# manual_slave.net
KiCad netlist of a schematic drawn in EAGLE
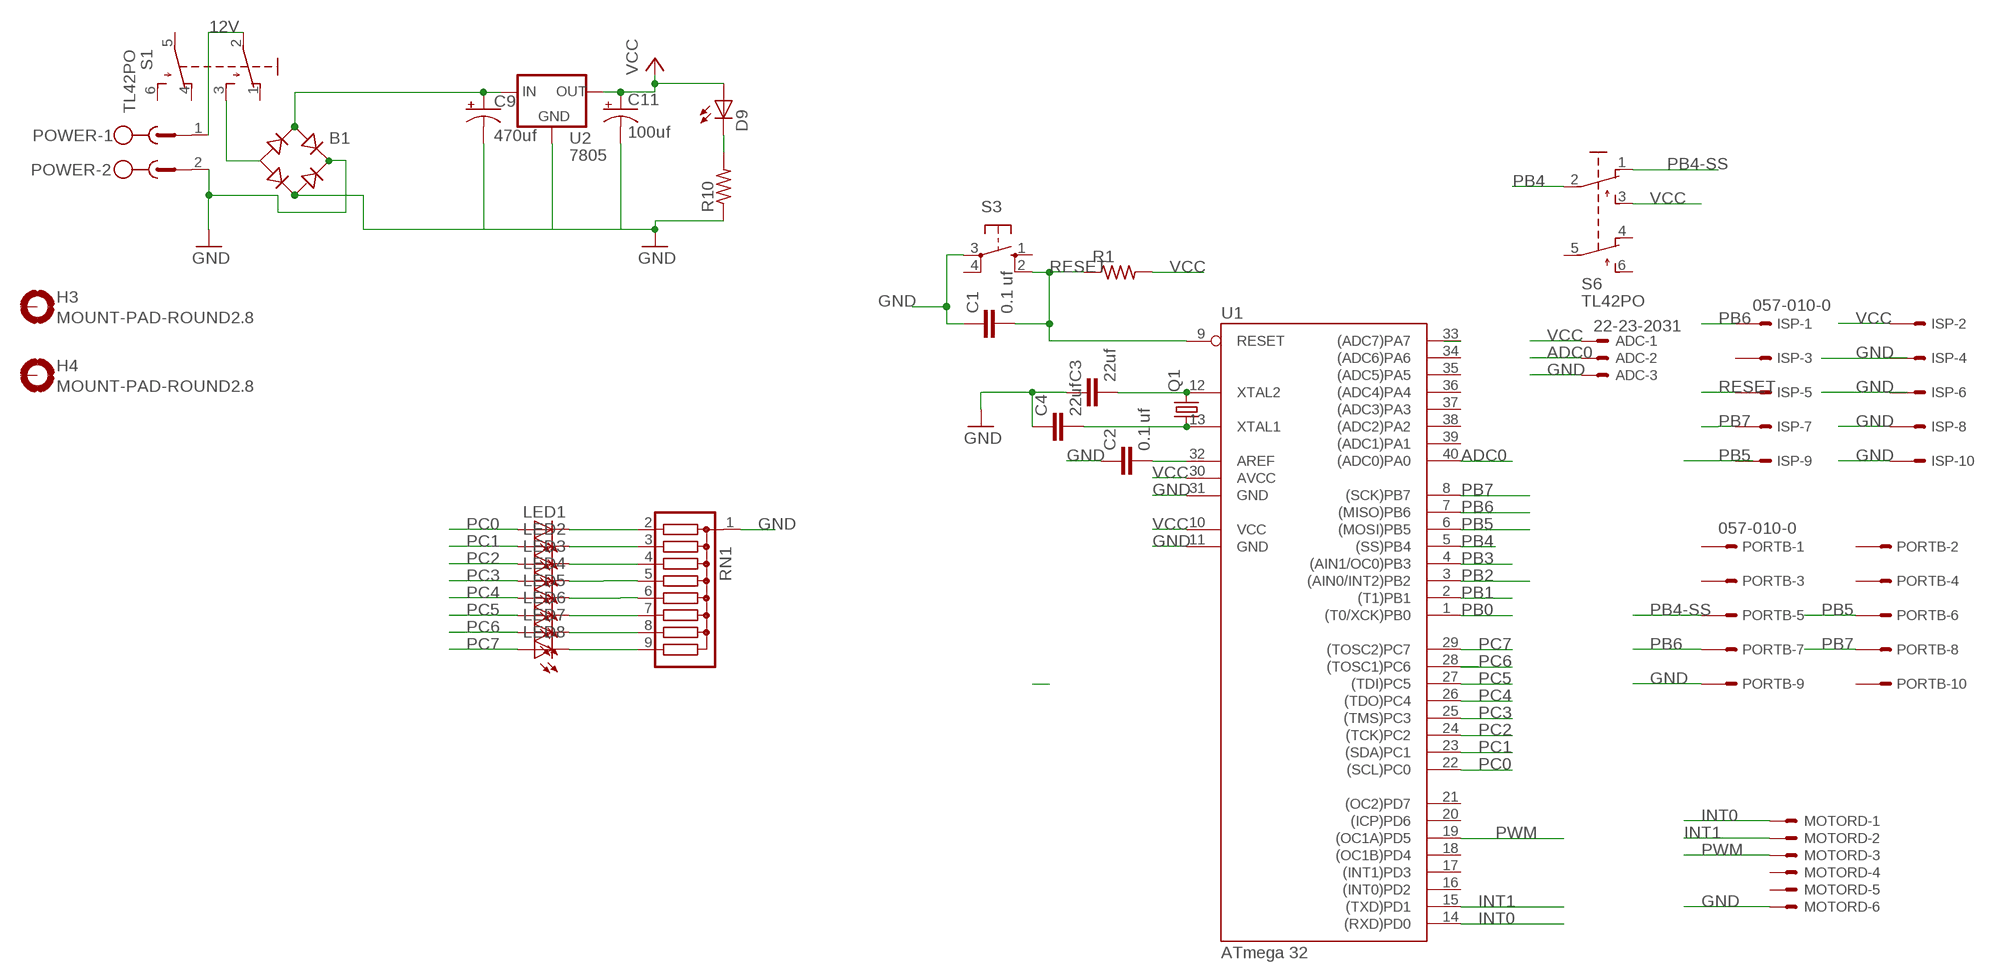
[diagram p0: schematic, sheet 1]

(export (version "E")
  (design (tool "Eeschema 10.0.6"))
  (components
    (comp (ref "ADC")
      (value "22-23-2031")
      (footprint "eagle-import:22-23-2031")
      (fields (field (name "MF") "MOLEX"))
      (libsource (lib "eagle-import") (part "22-23-2031"))
    )
    (comp (ref "B1")
      (value "RB1A")
      (footprint "eagle-import:RB1A")
      (libsource (lib "eagle-import") (part "RB1A"))
    )
    (comp (ref "C1")
      (value "0.1 uf")
      (footprint "eagle-import:C025-024X044")
      (libsource (lib "eagle-import") (part "C-EU025-024X044"))
    )
    (comp (ref "C2")
      (value "0.1 uf")
      (footprint "eagle-import:C025-024X044")
      (libsource (lib "eagle-import") (part "C-EU025-024X044"))
    )
    (comp (ref "C3")
      (value "22uf")
      (footprint "eagle-import:C025-024X044")
      (libsource (lib "eagle-import") (part "C-EU025-024X044"))
    )
    (comp (ref "C4")
      (value "22uf")
      (footprint "eagle-import:C025-024X044")
      (libsource (lib "eagle-import") (part "C-EU025-024X044"))
    )
    (comp (ref "C9")
      (value "470uf")
      (footprint "eagle-import:E2-4")
      (libsource (lib "eagle-import") (part "CPOL-USE2-4"))
    )
    (comp (ref "C11")
      (value "100uf")
      (footprint "eagle-import:E2-4")
      (libsource (lib "eagle-import") (part "CPOL-USE2-4"))
    )
    (comp (ref "D9")
      (value "LED3MM")
      (footprint "eagle-import:LED3MM")
      (libsource (lib "eagle-import") (part "LED3MM"))
    )
    (comp (ref "H3")
      (value "MOUNT-PAD-ROUND2.8")
      (footprint "eagle-import:2,8-PAD")
      (libsource (lib "eagle-import") (part "MOUNT-PAD-ROUND2.8"))
    )
    (comp (ref "H4")
      (value "MOUNT-PAD-ROUND2.8")
      (footprint "eagle-import:2,8-PAD")
      (libsource (lib "eagle-import") (part "MOUNT-PAD-ROUND2.8"))
    )
    (comp (ref "ISP")
      (value "057-010-0")
      (footprint "eagle-import:057-010-0")
      (libsource (lib "eagle-import") (part "057-010-0"))
    )
    (comp (ref "LED1")
      (value "LED3MM")
      (footprint "eagle-import:LED3MM")
      (libsource (lib "eagle-import") (part "LED3MM"))
    )
    (comp (ref "LED2")
      (value "LED3MM")
      (footprint "eagle-import:LED3MM")
      (libsource (lib "eagle-import") (part "LED3MM"))
    )
    (comp (ref "LED3")
      (value "LED3MM")
      (footprint "eagle-import:LED3MM")
      (libsource (lib "eagle-import") (part "LED3MM"))
    )
    (comp (ref "LED4")
      (value "LED3MM")
      (footprint "eagle-import:LED3MM")
      (libsource (lib "eagle-import") (part "LED3MM"))
    )
    (comp (ref "LED5")
      (value "LED3MM")
      (footprint "eagle-import:LED3MM")
      (libsource (lib "eagle-import") (part "LED3MM"))
    )
    (comp (ref "LED6")
      (value "LED3MM")
      (footprint "eagle-import:LED3MM")
      (libsource (lib "eagle-import") (part "LED3MM"))
    )
    (comp (ref "LED7")
      (value "LED3MM")
      (footprint "eagle-import:LED3MM")
      (libsource (lib "eagle-import") (part "LED3MM"))
    )
    (comp (ref "LED8")
      (value "LED3MM")
      (footprint "eagle-import:LED3MM")
      (libsource (lib "eagle-import") (part "LED3MM"))
    )
    (comp (ref "MOTORD")
      (value "22-23-2061")
      (footprint "eagle-import:22-23-2061")
      (fields (field (name "MF") "MOLEX"))
      (libsource (lib "eagle-import") (part "22-23-2061"))
    )
    (comp (ref "PORTB")
      (value "057-010-0")
      (footprint "eagle-import:057-010-0")
      (libsource (lib "eagle-import") (part "057-010-0"))
    )
    (comp (ref "POWER")
      (value "MSTBV2")
      (footprint "eagle-import:MSTBV2")
      (libsource (lib "eagle-import") (part "MSTBV2"))
    )
    (comp (ref "Q1")
      (value "CRYSTALHC18U-V")
      (footprint "eagle-import:HC18U-V")
      (libsource (lib "eagle-import") (part "CRYSTALHC18U-V"))
    )
    (comp (ref "R1")
      (value "R-US_0204/7")
      (footprint "eagle-import:0204_7")
      (libsource (lib "eagle-import") (part "R-US_0204/7"))
    )
    (comp (ref "R10")
      (value "R-US_0204/7")
      (footprint "eagle-import:0204_7")
      (libsource (lib "eagle-import") (part "R-US_0204/7"))
    )
    (comp (ref "RN1")
      (value "G08R")
      (footprint "eagle-import:SIL9")
      (libsource (lib "eagle-import") (part "G08R"))
    )
    (comp (ref "S1")
      (value "TL42PO")
      (footprint "eagle-import:TL4XPO")
      (libsource (lib "eagle-import") (part "TL42PO"))
    )
    (comp (ref "S3")
      (value "10-XX")
      (footprint "eagle-import:B3F-10XX")
      (fields (field (name "MPN") "B3F-1000"))
      (libsource (lib "eagle-import") (part "10-XX"))
    )
    (comp (ref "S6")
      (value "TL42PO")
      (footprint "eagle-import:TL4XPO")
      (libsource (lib "eagle-import") (part "TL42PO"))
    )
    (comp (ref "U1")
      (value "ATmega 32")
      (footprint "eagle-import:DIL40")
      (fields (field (name "MPN") "ATMEGA32-16PU"))
      (libsource (lib "eagle-import") (part "MEGA32-P"))
    )
    (comp (ref "U2")
      (value "7805")
      (footprint "eagle-import:78XXL")
      (libsource (lib "eagle-import") (part "78XXL"))
    )
  )
  (nets
    (net (code "1") (name "/12V") (class "Default")
      (node (ref "POWER") (pin "1") (pinfunction "SK_1") (pintype "passive"))
      (node (ref "S1") (pin "2") (pinfunction "P_2") (pintype "passive"))
    )
    (net (code "2") (name "/ADC0") (class "Default")
      (node (ref "ADC") (pin "2") (pinfunction "S_2") (pintype "passive"))
      (node (ref "U1") (pin "40") (pinfunction "(ADC0)PA0_40") (pintype "bidirectional"))
    )
    (net (code "3") (name "/INT0") (class "Default")
      (node (ref "MOTORD") (pin "1") (pinfunction "S_1") (pintype "passive"))
      (node (ref "U1") (pin "14") (pinfunction "(RXD)PD0_14") (pintype "bidirectional"))
    )
    (net (code "4") (name "/INT1") (class "Default")
      (node (ref "MOTORD") (pin "2") (pinfunction "S_2") (pintype "passive"))
      (node (ref "U1") (pin "15") (pinfunction "(TXD)PD1_15") (pintype "bidirectional"))
    )
    (net (code "5") (name "/PB0") (class "Default")
      (node (ref "U1") (pin "1") (pinfunction "(T0/XCK)PB0_1") (pintype "bidirectional"))
    )
    (net (code "6") (name "/PB1") (class "Default")
      (node (ref "U1") (pin "2") (pinfunction "(T1)PB1_2") (pintype "bidirectional"))
    )
    (net (code "7") (name "/PB2") (class "Default")
      (node (ref "U1") (pin "3") (pinfunction "(AIN0/INT2)PB2_3") (pintype "bidirectional"))
    )
    (net (code "8") (name "/PB3") (class "Default")
      (node (ref "U1") (pin "4") (pinfunction "(AIN1/OC0)PB3_4") (pintype "bidirectional"))
    )
    (net (code "9") (name "/PB4") (class "Default")
      (node (ref "S6") (pin "2") (pinfunction "P_2") (pintype "passive"))
      (node (ref "U1") (pin "5") (pinfunction "(SS)PB4_5") (pintype "bidirectional"))
    )
    (net (code "10") (name "/PB4-SS") (class "Default")
      (node (ref "PORTB") (pin "5") (pinfunction "S_5") (pintype "passive"))
      (node (ref "S6") (pin "1") (pinfunction "O_1") (pintype "passive"))
    )
    (net (code "11") (name "/PB5") (class "Default")
      (node (ref "ISP") (pin "9") (pinfunction "S_9") (pintype "passive"))
      (node (ref "PORTB") (pin "6") (pinfunction "S_6") (pintype "passive"))
      (node (ref "U1") (pin "6") (pinfunction "(MOSI)PB5_6") (pintype "bidirectional"))
    )
    (net (code "12") (name "/PB6") (class "Default")
      (node (ref "ISP") (pin "1") (pinfunction "S_1") (pintype "passive"))
      (node (ref "PORTB") (pin "7") (pinfunction "S_7") (pintype "passive"))
      (node (ref "U1") (pin "7") (pinfunction "(MISO)PB6_7") (pintype "bidirectional"))
    )
    (net (code "13") (name "/PB7") (class "Default")
      (node (ref "ISP") (pin "7") (pinfunction "S_7") (pintype "passive"))
      (node (ref "PORTB") (pin "8") (pinfunction "S_8") (pintype "passive"))
      (node (ref "U1") (pin "8") (pinfunction "(SCK)PB7_8") (pintype "bidirectional"))
    )
    (net (code "14") (name "/PC0") (class "Default")
      (node (ref "LED1") (pin "A") (pinfunction "A_A") (pintype "passive"))
      (node (ref "U1") (pin "22") (pinfunction "(SCL)PC0_22") (pintype "bidirectional"))
    )
    (net (code "15") (name "/PC1") (class "Default")
      (node (ref "LED2") (pin "A") (pinfunction "A_A") (pintype "passive"))
      (node (ref "U1") (pin "23") (pinfunction "(SDA)PC1_23") (pintype "bidirectional"))
    )
    (net (code "16") (name "/PC2") (class "Default")
      (node (ref "LED3") (pin "A") (pinfunction "A_A") (pintype "passive"))
      (node (ref "U1") (pin "24") (pinfunction "(TCK)PC2_24") (pintype "bidirectional"))
    )
    (net (code "17") (name "/PC3") (class "Default")
      (node (ref "LED4") (pin "A") (pinfunction "A_A") (pintype "passive"))
      (node (ref "U1") (pin "25") (pinfunction "(TMS)PC3_25") (pintype "bidirectional"))
    )
    (net (code "18") (name "/PC4") (class "Default")
      (node (ref "LED5") (pin "A") (pinfunction "A_A") (pintype "passive"))
      (node (ref "U1") (pin "26") (pinfunction "(TDO)PC4_26") (pintype "bidirectional"))
    )
    (net (code "19") (name "/PC5") (class "Default")
      (node (ref "LED6") (pin "A") (pinfunction "A_A") (pintype "passive"))
      (node (ref "U1") (pin "27") (pinfunction "(TDI)PC5_27") (pintype "bidirectional"))
    )
    (net (code "20") (name "/PC6") (class "Default")
      (node (ref "LED7") (pin "A") (pinfunction "A_A") (pintype "passive"))
      (node (ref "U1") (pin "28") (pinfunction "(TOSC1)PC6_28") (pintype "bidirectional"))
    )
    (net (code "21") (name "/PC7") (class "Default")
      (node (ref "LED8") (pin "A") (pinfunction "A_A") (pintype "passive"))
      (node (ref "U1") (pin "29") (pinfunction "(TOSC2)PC7_29") (pintype "bidirectional"))
    )
    (net (code "22") (name "/PWM") (class "Default")
      (node (ref "MOTORD") (pin "3") (pinfunction "S_3") (pintype "passive"))
      (node (ref "U1") (pin "19") (pinfunction "(OC1A)PD5_19") (pintype "bidirectional"))
    )
    (net (code "23") (name "/RESET") (class "Default")
      (node (ref "C1") (pin "2") (pinfunction "2_2") (pintype "passive"))
      (node (ref "ISP") (pin "5") (pinfunction "S_5") (pintype "passive"))
      (node (ref "R1") (pin "1") (pinfunction "1_1") (pintype "passive"))
      (node (ref "S3") (pin "2") (pinfunction "S1_2") (pintype "passive"))
      (node (ref "U1") (pin "9") (pinfunction "RESET_9") (pintype "input"))
    )
    (net (code "24") (name "GND") (class "Default")
      (node (ref "ADC") (pin "3") (pinfunction "S_3") (pintype "passive"))
      (node (ref "B1") (pin "+") (pinfunction "+_+") (pintype "passive"))
      (node (ref "B1") (pin "AC2") (pinfunction "AC2_AC2") (pintype "passive"))
      (node (ref "C1") (pin "1") (pinfunction "1_1") (pintype "passive"))
      (node (ref "C11") (pin "-") (pinfunction "-_-") (pintype "passive"))
      (node (ref "C2") (pin "1") (pinfunction "1_1") (pintype "passive"))
      (node (ref "C3") (pin "1") (pinfunction "1_1") (pintype "passive"))
      (node (ref "C4") (pin "1") (pinfunction "1_1") (pintype "passive"))
      (node (ref "C9") (pin "-") (pinfunction "-_-") (pintype "passive"))
      (node (ref "ISP") (pin "10") (pinfunction "S_10") (pintype "passive"))
      (node (ref "ISP") (pin "4") (pinfunction "S_4") (pintype "passive"))
      (node (ref "ISP") (pin "6") (pinfunction "S_6") (pintype "passive"))
      (node (ref "ISP") (pin "8") (pinfunction "S_8") (pintype "passive"))
      (node (ref "MOTORD") (pin "6") (pinfunction "S_6") (pintype "passive"))
      (node (ref "PORTB") (pin "9") (pinfunction "S_9") (pintype "passive"))
      (node (ref "POWER") (pin "2") (pinfunction "SK_2") (pintype "passive"))
      (node (ref "R10") (pin "1") (pinfunction "1_1") (pintype "passive"))
      (node (ref "RN1") (pin "1") (pinfunction "1_1") (pintype "passive"))
      (node (ref "S3") (pin "3") (pinfunction "P_3") (pintype "passive"))
      (node (ref "U1") (pin "11") (pinfunction "GND_11") (pintype "power_in"))
      (node (ref "U1") (pin "31") (pinfunction "GND_31") (pintype "power_in"))
      (node (ref "U2") (pin "GND") (pinfunction "GND_GND") (pintype "input"))
    )
    (net (code "25") (name "Net-(B1-PadAC1)") (class "Default")
      (node (ref "B1") (pin "AC1") (pinfunction "AC1_AC1") (pintype "passive"))
      (node (ref "C9") (pin "+") (pinfunction "+_+") (pintype "passive"))
      (node (ref "U2") (pin "IN") (pinfunction "IN_IN") (pintype "input"))
    )
    (net (code "26") (name "Net-(D9-C)") (class "Default")
      (node (ref "D9") (pin "K") (pinfunction "C_K") (pintype "passive"))
      (node (ref "R10") (pin "2") (pinfunction "2_2") (pintype "passive"))
    )
    (net (code "27") (name "Net-(LED1-C)") (class "Default")
      (node (ref "LED1") (pin "K") (pinfunction "C_K") (pintype "passive"))
      (node (ref "RN1") (pin "2") (pinfunction "2_2") (pintype "passive"))
    )
    (net (code "28") (name "Net-(LED2-C)") (class "Default")
      (node (ref "LED2") (pin "K") (pinfunction "C_K") (pintype "passive"))
      (node (ref "RN1") (pin "3") (pinfunction "3_3") (pintype "passive"))
    )
    (net (code "29") (name "Net-(LED3-C)") (class "Default")
      (node (ref "LED3") (pin "K") (pinfunction "C_K") (pintype "passive"))
      (node (ref "RN1") (pin "4") (pinfunction "4_4") (pintype "passive"))
    )
    (net (code "30") (name "Net-(LED4-C)") (class "Default")
      (node (ref "LED4") (pin "K") (pinfunction "C_K") (pintype "passive"))
      (node (ref "RN1") (pin "5") (pinfunction "5_5") (pintype "passive"))
    )
    (net (code "31") (name "Net-(LED5-C)") (class "Default")
      (node (ref "LED5") (pin "K") (pinfunction "C_K") (pintype "passive"))
      (node (ref "RN1") (pin "6") (pinfunction "6_6") (pintype "passive"))
    )
    (net (code "32") (name "Net-(LED6-C)") (class "Default")
      (node (ref "LED6") (pin "K") (pinfunction "C_K") (pintype "passive"))
      (node (ref "RN1") (pin "7") (pinfunction "7_7") (pintype "passive"))
    )
    (net (code "33") (name "Net-(LED7-C)") (class "Default")
      (node (ref "LED7") (pin "K") (pinfunction "C_K") (pintype "passive"))
      (node (ref "RN1") (pin "8") (pinfunction "8_8") (pintype "passive"))
    )
    (net (code "34") (name "Net-(LED8-C)") (class "Default")
      (node (ref "LED8") (pin "K") (pinfunction "C_K") (pintype "passive"))
      (node (ref "RN1") (pin "9") (pinfunction "9_9") (pintype "passive"))
    )
    (net (code "35") (name "Net-(S1-S)") (class "Default")
      (node (ref "B1") (pin "-") (pinfunction "-_-") (pintype "passive"))
      (node (ref "S1") (pin "3") (pinfunction "S_3") (pintype "passive"))
    )
    (net (code "36") (name "Net-(U1-AREF)") (class "Default")
      (node (ref "C2") (pin "2") (pinfunction "2_2") (pintype "passive"))
      (node (ref "U1") (pin "32") (pinfunction "AREF_32") (pintype "passive"))
    )
    (net (code "37") (name "Net-(U1-XTAL1)") (class "Default")
      (node (ref "C4") (pin "2") (pinfunction "2_2") (pintype "passive"))
      (node (ref "Q1") (pin "1") (pinfunction "1_1") (pintype "passive"))
      (node (ref "U1") (pin "13") (pinfunction "XTAL1_13") (pintype "bidirectional"))
    )
    (net (code "38") (name "Net-(U1-XTAL2)") (class "Default")
      (node (ref "C3") (pin "2") (pinfunction "2_2") (pintype "passive"))
      (node (ref "Q1") (pin "2") (pinfunction "2_2") (pintype "passive"))
      (node (ref "U1") (pin "12") (pinfunction "XTAL2_12") (pintype "bidirectional"))
    )
    (net (code "39") (name "VCC") (class "Default")
      (node (ref "ADC") (pin "1") (pinfunction "S_1") (pintype "passive"))
      (node (ref "C11") (pin "+") (pinfunction "+_+") (pintype "passive"))
      (node (ref "D9") (pin "A") (pinfunction "A_A") (pintype "passive"))
      (node (ref "ISP") (pin "2") (pinfunction "S_2") (pintype "passive"))
      (node (ref "R1") (pin "2") (pinfunction "2_2") (pintype "passive"))
      (node (ref "S6") (pin "3") (pinfunction "S_3") (pintype "passive"))
      (node (ref "U1") (pin "10") (pinfunction "VCC_10") (pintype "power_in"))
      (node (ref "U1") (pin "30") (pinfunction "AVCC_30") (pintype "power_in"))
      (node (ref "U2") (pin "OUT") (pinfunction "OUT_OUT") (pintype "passive"))
    )
    (net (code "40") (name "unconnected-(H3-MOUNT-PadB2,8)") (class "Default")
      (node (ref "H3") (pin "B2,8") (pinfunction "MOUNT_B2,8") (pintype "passive"))
    )
    (net (code "41") (name "unconnected-(H4-MOUNT-PadB2,8)") (class "Default")
      (node (ref "H4") (pin "B2,8") (pinfunction "MOUNT_B2,8") (pintype "passive"))
    )
    (net (code "42") (name "unconnected-(ISPD-S-Pad3)") (class "Default")
      (node (ref "ISP") (pin "3") (pinfunction "S_3") (pintype "passive"))
    )
    (net (code "43") (name "unconnected-(MOTORDD-S-Pad4)") (class "Default")
      (node (ref "MOTORD") (pin "4") (pinfunction "S_4") (pintype "passive"))
    )
    (net (code "44") (name "unconnected-(MOTORDE-S-Pad5)") (class "Default")
      (node (ref "MOTORD") (pin "5") (pinfunction "S_5") (pintype "passive"))
    )
    (net (code "45") (name "unconnected-(PORTBA-S-Pad1)") (class "Default")
      (node (ref "PORTB") (pin "1") (pinfunction "S_1") (pintype "passive"))
    )
    (net (code "46") (name "unconnected-(PORTBB-S-Pad10)") (class "Default")
      (node (ref "PORTB") (pin "10") (pinfunction "S_10") (pintype "passive"))
    )
    (net (code "47") (name "unconnected-(PORTBC-S-Pad2)") (class "Default")
      (node (ref "PORTB") (pin "2") (pinfunction "S_2") (pintype "passive"))
    )
    (net (code "48") (name "unconnected-(PORTBD-S-Pad3)") (class "Default")
      (node (ref "PORTB") (pin "3") (pinfunction "S_3") (pintype "passive"))
    )
    (net (code "49") (name "unconnected-(PORTBE-S-Pad4)") (class "Default")
      (node (ref "PORTB") (pin "4") (pinfunction "S_4") (pintype "passive"))
    )
    (net (code "50") (name "unconnected-(S1-O-Pad1)") (class "Default")
      (node (ref "S1") (pin "1") (pinfunction "O_1") (pintype "passive"))
    )
    (net (code "51") (name "unconnected-(S1-O1-Pad4)") (class "Default")
      (node (ref "S1") (pin "4") (pinfunction "O1_4") (pintype "passive"))
    )
    (net (code "52") (name "unconnected-(S1-P1-Pad5)") (class "Default")
      (node (ref "S1") (pin "5") (pinfunction "P1_5") (pintype "passive"))
    )
    (net (code "53") (name "unconnected-(S1-S1-Pad6)") (class "Default")
      (node (ref "S1") (pin "6") (pinfunction "S1_6") (pintype "passive"))
    )
    (net (code "54") (name "unconnected-(S3-P1-Pad4)") (class "Default")
      (node (ref "S3") (pin "4") (pinfunction "P1_4") (pintype "passive"))
    )
    (net (code "55") (name "unconnected-(S3-S-Pad1)") (class "Default")
      (node (ref "S3") (pin "1") (pinfunction "S_1") (pintype "passive"))
    )
    (net (code "56") (name "unconnected-(S6-O1-Pad4)") (class "Default")
      (node (ref "S6") (pin "4") (pinfunction "O1_4") (pintype "passive"))
    )
    (net (code "57") (name "unconnected-(S6-P1-Pad5)") (class "Default")
      (node (ref "S6") (pin "5") (pinfunction "P1_5") (pintype "passive"))
    )
    (net (code "58") (name "unconnected-(S6-S1-Pad6)") (class "Default")
      (node (ref "S6") (pin "6") (pinfunction "S1_6") (pintype "passive"))
    )
    (net (code "59") (name "unconnected-(U1-(ADC1)PA1-Pad39)") (class "Default")
      (node (ref "U1") (pin "39") (pinfunction "(ADC1)PA1_39") (pintype "bidirectional"))
    )
    (net (code "60") (name "unconnected-(U1-(ADC2)PA2-Pad38)") (class "Default")
      (node (ref "U1") (pin "38") (pinfunction "(ADC2)PA2_38") (pintype "bidirectional"))
    )
    (net (code "61") (name "unconnected-(U1-(ADC3)PA3-Pad37)") (class "Default")
      (node (ref "U1") (pin "37") (pinfunction "(ADC3)PA3_37") (pintype "bidirectional"))
    )
    (net (code "62") (name "unconnected-(U1-(ADC4)PA4-Pad36)") (class "Default")
      (node (ref "U1") (pin "36") (pinfunction "(ADC4)PA4_36") (pintype "bidirectional"))
    )
    (net (code "63") (name "unconnected-(U1-(ADC5)PA5-Pad35)") (class "Default")
      (node (ref "U1") (pin "35") (pinfunction "(ADC5)PA5_35") (pintype "bidirectional"))
    )
    (net (code "64") (name "unconnected-(U1-(ADC6)PA6-Pad34)") (class "Default")
      (node (ref "U1") (pin "34") (pinfunction "(ADC6)PA6_34") (pintype "bidirectional"))
    )
    (net (code "65") (name "unconnected-(U1-(ADC7)PA7-Pad33)") (class "Default")
      (node (ref "U1") (pin "33") (pinfunction "(ADC7)PA7_33") (pintype "bidirectional"))
    )
    (net (code "66") (name "unconnected-(U1-(ICP)PD6-Pad20)") (class "Default")
      (node (ref "U1") (pin "20") (pinfunction "(ICP)PD6_20") (pintype "bidirectional"))
    )
    (net (code "67") (name "unconnected-(U1-(INT0)PD2-Pad16)") (class "Default")
      (node (ref "U1") (pin "16") (pinfunction "(INT0)PD2_16") (pintype "bidirectional"))
    )
    (net (code "68") (name "unconnected-(U1-(INT1)PD3-Pad17)") (class "Default")
      (node (ref "U1") (pin "17") (pinfunction "(INT1)PD3_17") (pintype "bidirectional"))
    )
    (net (code "69") (name "unconnected-(U1-(OC1B)PD4-Pad18)") (class "Default")
      (node (ref "U1") (pin "18") (pinfunction "(OC1B)PD4_18") (pintype "bidirectional"))
    )
    (net (code "70") (name "unconnected-(U1-(OC2)PD7-Pad21)") (class "Default")
      (node (ref "U1") (pin "21") (pinfunction "(OC2)PD7_21") (pintype "bidirectional"))
    )
  )
)
